# connection.net
KiCad netlist of a schematic drawn in EAGLE
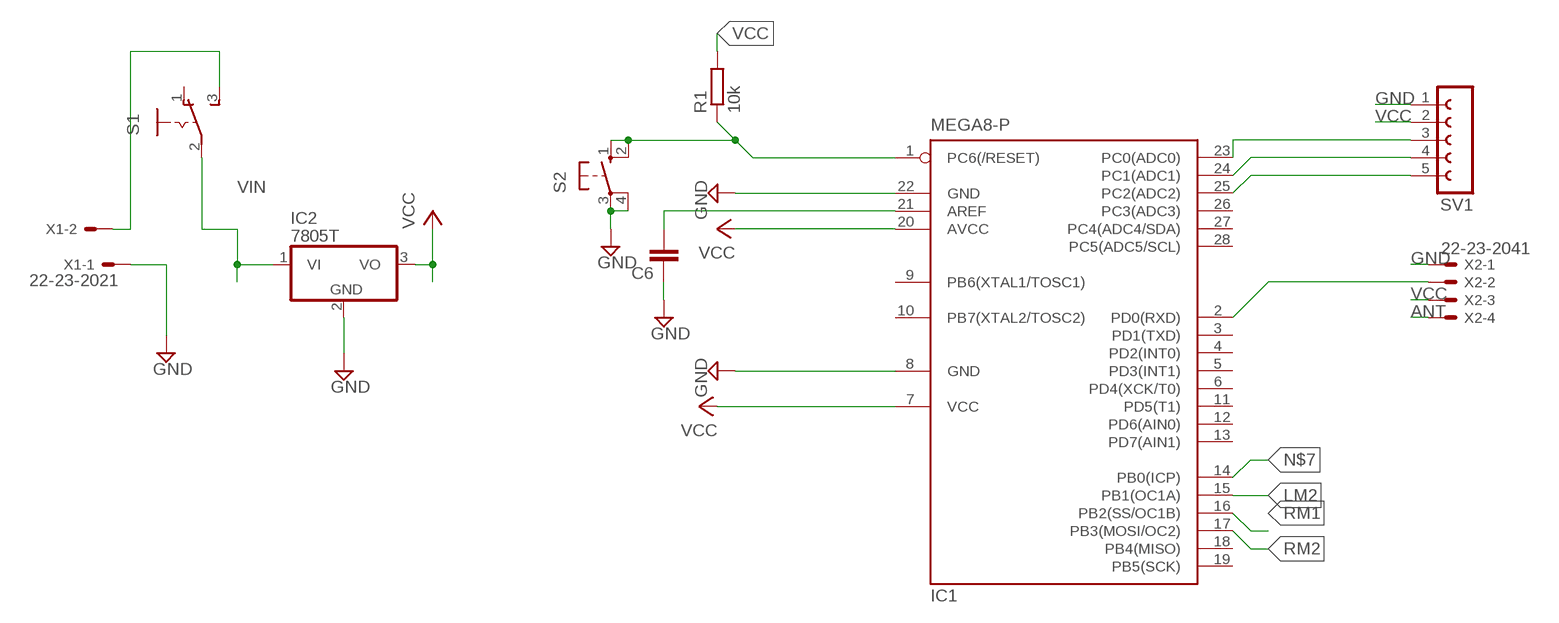
[diagram p0: schematic, sheet 1]

(export (version "E")
  (design (tool "Eeschema 10.0.6"))
  (components
    (comp (ref "C6")
      (value "C5/2.5")
      (footprint "eagle-import:C5B2.5")
      (libsource (lib "eagle-import") (part "C5/2.5"))
    )
    (comp (ref "IC1")
      (value "MEGA8-P")
      (footprint "eagle-import:DIL28-3")
      (libsource (lib "eagle-import") (part "MEGA8-P"))
    )
    (comp (ref "IC2")
      (value "7805T")
      (footprint "eagle-import:TO220H")
      (libsource (lib "eagle-import") (part "78T05"))
    )
    (comp (ref "R1")
      (value "10k")
      (footprint "eagle-import:0207_10")
      (libsource (lib "eagle-import") (part "R-EU_0207/10"))
    )
    (comp (ref "S1")
      (value "255SB")
      (footprint "eagle-import:255SB")
      (libsource (lib "eagle-import") (part "255SB"))
    )
    (comp (ref "S2")
      (value "10-XX")
      (footprint "eagle-import:B3F-10XX")
      (fields (field (name "MPN") "B3F-1000"))
      (libsource (lib "eagle-import") (part "10-XX"))
    )
    (comp (ref "SV1")
      (value "FE05W")
      (footprint "eagle-import:FE05W")
      (libsource (lib "eagle-import") (part "FE05W"))
    )
    (comp (ref "X1")
      (value "22-23-2021")
      (footprint "eagle-import:22-23-2021")
      (fields (field (name "MF") "MOLEX"))
      (libsource (lib "eagle-import") (part "22-23-2021"))
    )
    (comp (ref "X2")
      (value "22-23-2041")
      (footprint "eagle-import:22-23-2041")
      (fields (field (name "MF") "MOLEX"))
      (libsource (lib "eagle-import") (part "22-23-2041"))
    )
  )
  (nets
    (net (code "1") (name "/ANT") (class "Default")
      (node (ref "X2") (pin "4") (pinfunction "S_4") (pintype "passive"))
    )
    (net (code "2") (name "/VIN") (class "Default")
      (node (ref "IC2") (pin "1") (pinfunction "VI_1") (pintype "input"))
      (node (ref "S1") (pin "2") (pinfunction "P_2") (pintype "passive"))
    )
    (net (code "3") (name "GND") (class "Default")
      (node (ref "C6") (pin "1") (pinfunction "1_1") (pintype "passive"))
      (node (ref "IC1") (pin "22") (pinfunction "GND_22") (pintype "power_in"))
      (node (ref "IC1") (pin "8") (pinfunction "GND_8") (pintype "power_in"))
      (node (ref "IC2") (pin "2") (pinfunction "GND_2") (pintype "passive"))
      (node (ref "S2") (pin "3") (pinfunction "P_3") (pintype "passive"))
      (node (ref "S2") (pin "4") (pinfunction "P1_4") (pintype "passive"))
      (node (ref "SV1") (pin "1") (pinfunction "1_1") (pintype "passive"))
      (node (ref "X1") (pin "1") (pinfunction "S_1") (pintype "passive"))
      (node (ref "X2") (pin "1") (pinfunction "S_1") (pintype "passive"))
    )
    (net (code "4") (name "LM2") (class "Default")
      (node (ref "IC1") (pin "15") (pinfunction "PB1(OC1A)_15") (pintype "bidirectional"))
    )
    (net (code "5") (name "N$7") (class "Default")
      (node (ref "IC1") (pin "14") (pinfunction "PB0(ICP)_14") (pintype "bidirectional"))
    )
    (net (code "6") (name "Net-(IC1-AREF)") (class "Default")
      (node (ref "C6") (pin "2") (pinfunction "2_2") (pintype "passive"))
      (node (ref "IC1") (pin "21") (pinfunction "AREF_21") (pintype "passive"))
    )
    (net (code "7") (name "Net-(IC1-PC0(ADC0))") (class "Default")
      (node (ref "IC1") (pin "23") (pinfunction "PC0(ADC0)_23") (pintype "bidirectional"))
      (node (ref "SV1") (pin "3") (pinfunction "3_3") (pintype "passive"))
    )
    (net (code "8") (name "Net-(IC1-PC1(ADC1))") (class "Default")
      (node (ref "IC1") (pin "24") (pinfunction "PC1(ADC1)_24") (pintype "bidirectional"))
      (node (ref "SV1") (pin "4") (pinfunction "4_4") (pintype "passive"))
    )
    (net (code "9") (name "Net-(IC1-PC2(ADC2))") (class "Default")
      (node (ref "IC1") (pin "25") (pinfunction "PC2(ADC2)_25") (pintype "bidirectional"))
      (node (ref "SV1") (pin "5") (pinfunction "5_5") (pintype "passive"))
    )
    (net (code "10") (name "Net-(IC1-PC6({slash}RESET))") (class "Default")
      (node (ref "IC1") (pin "1") (pinfunction "PC6(/RESET)_1") (pintype "bidirectional"))
      (node (ref "R1") (pin "1") (pinfunction "1_1") (pintype "passive"))
      (node (ref "S2") (pin "1") (pinfunction "S_1") (pintype "passive"))
      (node (ref "S2") (pin "2") (pinfunction "S1_2") (pintype "passive"))
    )
    (net (code "11") (name "Net-(IC1-PD0(RXD))") (class "Default")
      (node (ref "IC1") (pin "2") (pinfunction "PD0(RXD)_2") (pintype "bidirectional"))
      (node (ref "X2") (pin "2") (pinfunction "S_2") (pintype "passive"))
    )
    (net (code "12") (name "Net-(S1-S)") (class "Default")
      (node (ref "S1") (pin "3") (pinfunction "S_3") (pintype "passive"))
      (node (ref "X1") (pin "2") (pinfunction "S_2") (pintype "passive"))
    )
    (net (code "13") (name "RM1") (class "Default")
      (node (ref "IC1") (pin "16") (pinfunction "PB2(SS/OC1B)_16") (pintype "bidirectional"))
    )
    (net (code "14") (name "RM2") (class "Default")
      (node (ref "IC1") (pin "17") (pinfunction "PB3(MOSI/OC2)_17") (pintype "bidirectional"))
    )
    (net (code "15") (name "VCC") (class "Default")
      (node (ref "IC1") (pin "20") (pinfunction "AVCC_20") (pintype "power_in"))
      (node (ref "IC1") (pin "7") (pinfunction "VCC_7") (pintype "power_in"))
      (node (ref "IC2") (pin "3") (pinfunction "VO_3") (pintype "passive"))
      (node (ref "R1") (pin "2") (pinfunction "2_2") (pintype "passive"))
      (node (ref "SV1") (pin "2") (pinfunction "2_2") (pintype "passive"))
      (node (ref "X2") (pin "3") (pinfunction "S_3") (pintype "passive"))
    )
    (net (code "16") (name "unconnected-(IC1-PB4(MISO)-Pad18)") (class "Default")
      (node (ref "IC1") (pin "18") (pinfunction "PB4(MISO)_18") (pintype "bidirectional"))
    )
    (net (code "17") (name "unconnected-(IC1-PB5(SCK)-Pad19)") (class "Default")
      (node (ref "IC1") (pin "19") (pinfunction "PB5(SCK)_19") (pintype "bidirectional"))
    )
    (net (code "18") (name "unconnected-(IC1-PB6(XTAL1{slash}TOSC1)-Pad9)") (class "Default")
      (node (ref "IC1") (pin "9") (pinfunction "PB6(XTAL1/TOSC1)_9") (pintype "bidirectional"))
    )
    (net (code "19") (name "unconnected-(IC1-PB7(XTAL2{slash}TOSC2)-Pad10)") (class "Default")
      (node (ref "IC1") (pin "10") (pinfunction "PB7(XTAL2/TOSC2)_10") (pintype "bidirectional"))
    )
    (net (code "20") (name "unconnected-(IC1-PC3(ADC3)-Pad26)") (class "Default")
      (node (ref "IC1") (pin "26") (pinfunction "PC3(ADC3)_26") (pintype "bidirectional"))
    )
    (net (code "21") (name "unconnected-(IC1-PC4(ADC4{slash}SDA)-Pad27)") (class "Default")
      (node (ref "IC1") (pin "27") (pinfunction "PC4(ADC4/SDA)_27") (pintype "bidirectional"))
    )
    (net (code "22") (name "unconnected-(IC1-PC5(ADC5{slash}SCL)-Pad28)") (class "Default")
      (node (ref "IC1") (pin "28") (pinfunction "PC5(ADC5/SCL)_28") (pintype "bidirectional"))
    )
    (net (code "23") (name "unconnected-(IC1-PD1(TXD)-Pad3)") (class "Default")
      (node (ref "IC1") (pin "3") (pinfunction "PD1(TXD)_3") (pintype "bidirectional"))
    )
    (net (code "24") (name "unconnected-(IC1-PD2(INT0)-Pad4)") (class "Default")
      (node (ref "IC1") (pin "4") (pinfunction "PD2(INT0)_4") (pintype "bidirectional"))
    )
    (net (code "25") (name "unconnected-(IC1-PD3(INT1)-Pad5)") (class "Default")
      (node (ref "IC1") (pin "5") (pinfunction "PD3(INT1)_5") (pintype "bidirectional"))
    )
    (net (code "26") (name "unconnected-(IC1-PD4(XCK{slash}T0)-Pad6)") (class "Default")
      (node (ref "IC1") (pin "6") (pinfunction "PD4(XCK/T0)_6") (pintype "bidirectional"))
    )
    (net (code "27") (name "unconnected-(IC1-PD5(T1)-Pad11)") (class "Default")
      (node (ref "IC1") (pin "11") (pinfunction "PD5(T1)_11") (pintype "bidirectional"))
    )
    (net (code "28") (name "unconnected-(IC1-PD6(AIN0)-Pad12)") (class "Default")
      (node (ref "IC1") (pin "12") (pinfunction "PD6(AIN0)_12") (pintype "bidirectional"))
    )
    (net (code "29") (name "unconnected-(IC1-PD7(AIN1)-Pad13)") (class "Default")
      (node (ref "IC1") (pin "13") (pinfunction "PD7(AIN1)_13") (pintype "bidirectional"))
    )
    (net (code "30") (name "unconnected-(S1-O-Pad1)") (class "Default")
      (node (ref "S1") (pin "1") (pinfunction "O_1") (pintype "passive"))
    )
  )
)
